# 7segement4digits1badidea-max7219-smd-mk-.net
KiCad netlist of a schematic drawn in EAGLE
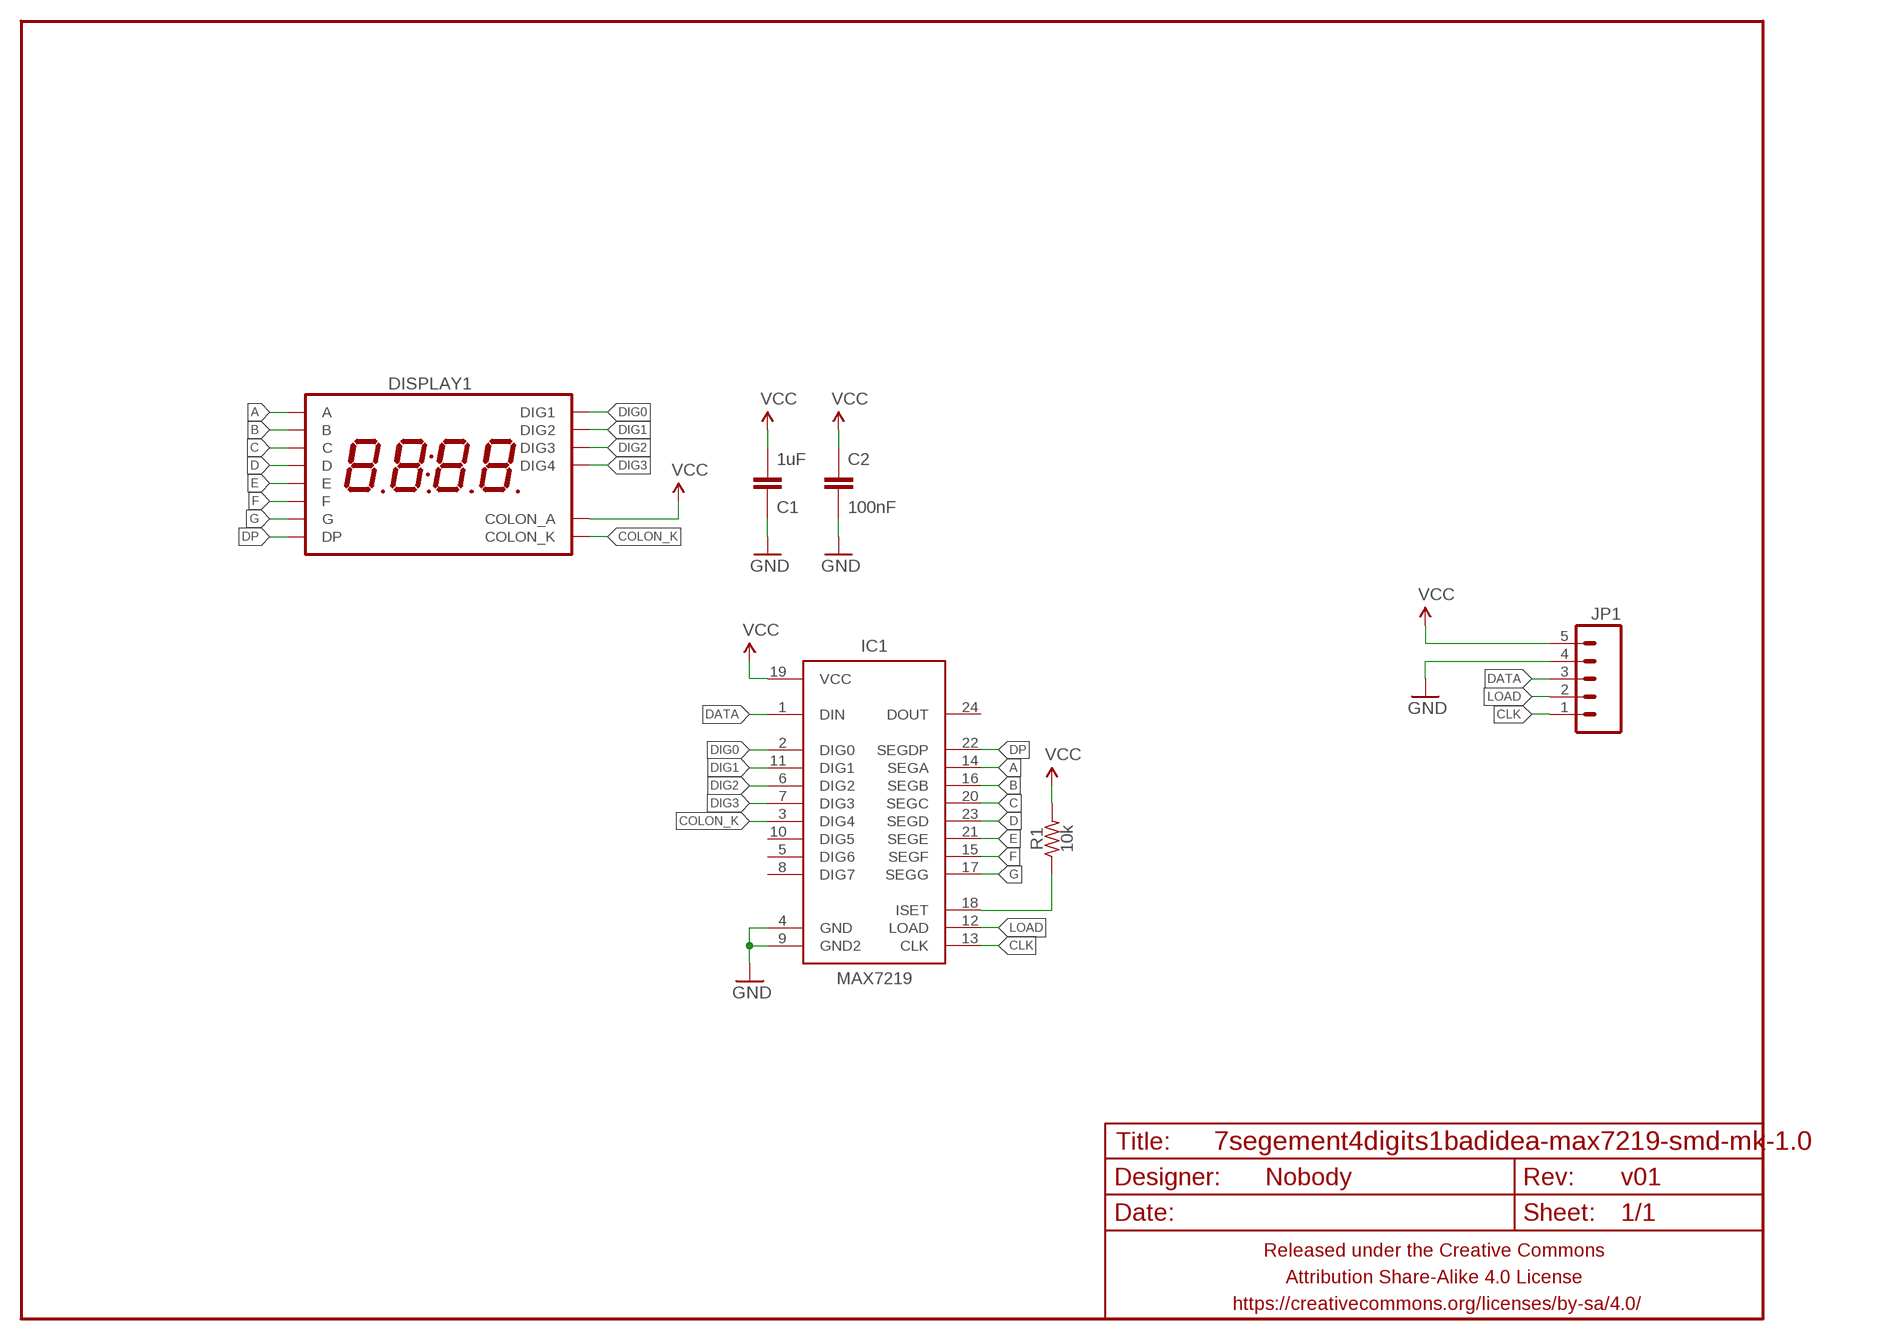
[diagram p0: schematic, sheet 1]

(export (version "E")
  (design (tool "Eeschema 10.0.6"))
  (components
    (comp (ref "C1")
      (value "1uF")
      (footprint "eagle-import:C0805")
      (libsource (lib "eagle-import") (part "CAPACITOR-CERAMICC0805"))
    )
    (comp (ref "C2")
      (value "100nF")
      (footprint "eagle-import:C0805")
      (libsource (lib "eagle-import") (part "CAPACITOR-CERAMICC0805"))
    )
    (comp (ref "DISPLAY1")
      (value "7SEG_4DIGIT_COLONADAFRUIT_0.56IN")
      (footprint "eagle-import:7SEG_4DIG")
      (libsource (lib "eagle-import") (part "7SEG_4DIGIT_COLONADAFRUIT_0.56IN"))
    )
    (comp (ref "FRAME1")
      (value "FRAME-LETTERNO_PACKAGE")
      (footprint "eagle-import:DUMMY")
      (fields (field (name "DESIGNER") "Nobody"))
      (libsource (lib "eagle-import") (part "FRAME-LETTERNO_PACKAGE"))
    )
    (comp (ref "IC1")
      (value "MAX7219")
      (footprint "eagle-import:SO24W")
      (libsource (lib "eagle-import") (part "MAX7219SOIC-W"))
    )
    (comp (ref "JP1")
      (value "M05JST-PH-VERT-PTH")
      (footprint "eagle-import:JST-5-PH-VERT-PTH")
      (libsource (lib "eagle-import") (part "M05JST-PH-VERT-PTH"))
    )
    (comp (ref "R1")
      (value "10k")
      (footprint "eagle-import:R0805")
      (libsource (lib "eagle-import") (part "RESISTORR0805"))
    )
  )
  (nets
    (net (code "1") (name "A") (class "Default")
      (node (ref "DISPLAY1") (pin "P$13") (pinfunction "A_P$13") (pintype "passive"))
      (node (ref "IC1") (pin "14") (pinfunction "SEGA_14") (pintype "bidirectional"))
    )
    (net (code "2") (name "B") (class "Default")
      (node (ref "DISPLAY1") (pin "P$9") (pinfunction "B_P$9") (pintype "passive"))
      (node (ref "IC1") (pin "16") (pinfunction "SEGB_16") (pintype "bidirectional"))
    )
    (net (code "3") (name "C") (class "Default")
      (node (ref "DISPLAY1") (pin "P$4") (pinfunction "C_P$4") (pintype "passive"))
      (node (ref "IC1") (pin "20") (pinfunction "SEGC_20") (pintype "bidirectional"))
    )
    (net (code "4") (name "CLK") (class "Default")
      (node (ref "IC1") (pin "13") (pinfunction "CLK_13") (pintype "bidirectional"))
      (node (ref "JP1") (pin "1") (pinfunction "1_1") (pintype "passive"))
    )
    (net (code "5") (name "COLON_K") (class "Default")
      (node (ref "DISPLAY1") (pin "P$7") (pinfunction "COLON_K_P$7") (pintype "passive"))
      (node (ref "IC1") (pin "3") (pinfunction "DIG4_3") (pintype "bidirectional"))
    )
    (net (code "6") (name "D") (class "Default")
      (node (ref "DISPLAY1") (pin "P$2") (pinfunction "D_P$2") (pintype "passive"))
      (node (ref "IC1") (pin "23") (pinfunction "SEGD_23") (pintype "bidirectional"))
    )
    (net (code "7") (name "DATA") (class "Default")
      (node (ref "IC1") (pin "1") (pinfunction "DIN_1") (pintype "bidirectional"))
      (node (ref "JP1") (pin "3") (pinfunction "3_3") (pintype "passive"))
    )
    (net (code "8") (name "DIG0") (class "Default")
      (node (ref "DISPLAY1") (pin "P$14") (pinfunction "DIG1_P$14") (pintype "passive"))
      (node (ref "IC1") (pin "2") (pinfunction "DIG0_2") (pintype "bidirectional"))
    )
    (net (code "9") (name "DIG1") (class "Default")
      (node (ref "DISPLAY1") (pin "P$11") (pinfunction "DIG2_P$11") (pintype "passive"))
      (node (ref "IC1") (pin "11") (pinfunction "DIG1_11") (pintype "bidirectional"))
    )
    (net (code "10") (name "DIG2") (class "Default")
      (node (ref "DISPLAY1") (pin "P$10") (pinfunction "DIG3_P$10") (pintype "passive"))
      (node (ref "IC1") (pin "6") (pinfunction "DIG2_6") (pintype "bidirectional"))
    )
    (net (code "11") (name "DIG3") (class "Default")
      (node (ref "DISPLAY1") (pin "P$6") (pinfunction "DIG4_P$6") (pintype "passive"))
      (node (ref "IC1") (pin "7") (pinfunction "DIG3_7") (pintype "bidirectional"))
    )
    (net (code "12") (name "DP") (class "Default")
      (node (ref "DISPLAY1") (pin "P$3") (pinfunction "DP_P$3") (pintype "passive"))
      (node (ref "IC1") (pin "22") (pinfunction "SEGDP_22") (pintype "bidirectional"))
    )
    (net (code "13") (name "E") (class "Default")
      (node (ref "DISPLAY1") (pin "P$1") (pinfunction "E_P$1") (pintype "passive"))
      (node (ref "IC1") (pin "21") (pinfunction "SEGE_21") (pintype "bidirectional"))
    )
    (net (code "14") (name "F") (class "Default")
      (node (ref "DISPLAY1") (pin "P$12") (pinfunction "F_P$12") (pintype "passive"))
      (node (ref "IC1") (pin "15") (pinfunction "SEGF_15") (pintype "bidirectional"))
    )
    (net (code "15") (name "G") (class "Default")
      (node (ref "DISPLAY1") (pin "P$5") (pinfunction "G_P$5") (pintype "passive"))
      (node (ref "IC1") (pin "17") (pinfunction "SEGG_17") (pintype "bidirectional"))
    )
    (net (code "16") (name "GND") (class "Default")
      (node (ref "C1") (pin "1") (pinfunction "1_1") (pintype "passive"))
      (node (ref "C2") (pin "2") (pinfunction "2_2") (pintype "passive"))
      (node (ref "IC1") (pin "4") (pinfunction "GND_4") (pintype "bidirectional"))
      (node (ref "IC1") (pin "9") (pinfunction "GND2_9") (pintype "bidirectional"))
      (node (ref "JP1") (pin "4") (pinfunction "4_4") (pintype "passive"))
    )
    (net (code "17") (name "LOAD") (class "Default")
      (node (ref "IC1") (pin "12") (pinfunction "LOAD_12") (pintype "bidirectional"))
      (node (ref "JP1") (pin "2") (pinfunction "2_2") (pintype "passive"))
    )
    (net (code "18") (name "Net-(IC1-ISET)") (class "Default")
      (node (ref "IC1") (pin "18") (pinfunction "ISET_18") (pintype "bidirectional"))
      (node (ref "R1") (pin "1") (pinfunction "1_1") (pintype "passive"))
    )
    (net (code "19") (name "VCC") (class "Default")
      (node (ref "C1") (pin "2") (pinfunction "2_2") (pintype "passive"))
      (node (ref "C2") (pin "1") (pinfunction "1_1") (pintype "passive"))
      (node (ref "DISPLAY1") (pin "P$8") (pinfunction "COLON_A_P$8") (pintype "passive"))
      (node (ref "IC1") (pin "19") (pinfunction "VCC_19") (pintype "bidirectional"))
      (node (ref "JP1") (pin "5") (pinfunction "5_5") (pintype "passive"))
      (node (ref "R1") (pin "2") (pinfunction "2_2") (pintype "passive"))
    )
    (net (code "20") (name "unconnected-(IC1-DIG5-Pad10)") (class "Default")
      (node (ref "IC1") (pin "10") (pinfunction "DIG5_10") (pintype "bidirectional"))
    )
    (net (code "21") (name "unconnected-(IC1-DIG6-Pad5)") (class "Default")
      (node (ref "IC1") (pin "5") (pinfunction "DIG6_5") (pintype "bidirectional"))
    )
    (net (code "22") (name "unconnected-(IC1-DIG7-Pad8)") (class "Default")
      (node (ref "IC1") (pin "8") (pinfunction "DIG7_8") (pintype "bidirectional"))
    )
    (net (code "23") (name "unconnected-(IC1-DOUT-Pad24)") (class "Default")
      (node (ref "IC1") (pin "24") (pinfunction "DOUT_24") (pintype "bidirectional"))
    )
  )
)
